# ControlAccess.net
KiCad netlist of a schematic drawn in Altium Designer
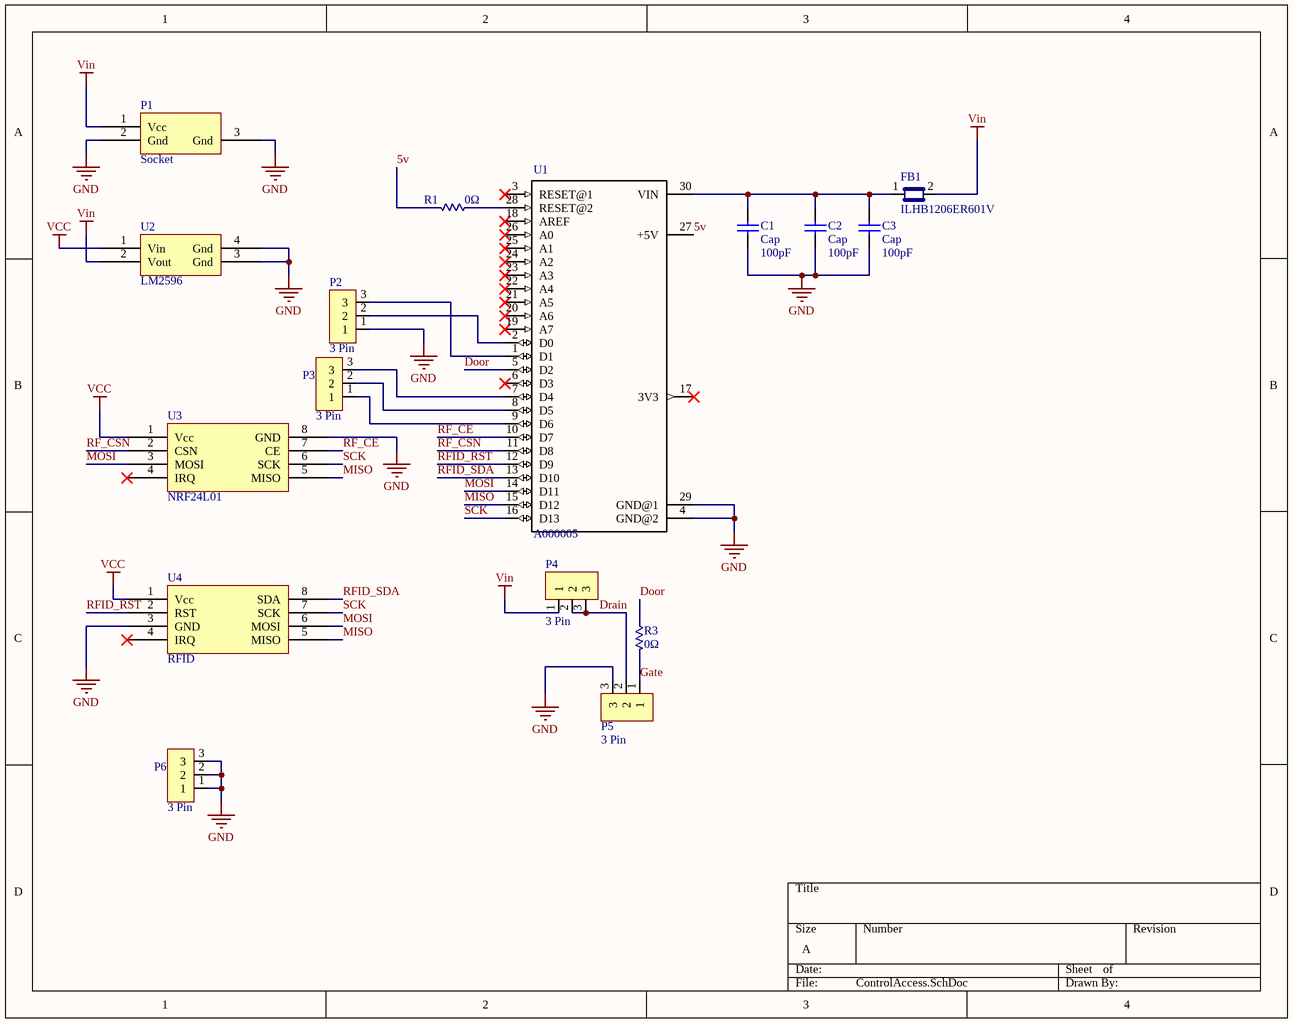
[diagram p0: ControlAccess.SchDoc]

(export (version "E")
  (design (tool "Eeschema 10.0.6"))
  (components
    (comp (ref "C1")
      (value "Cap")
      (footprint "RAD-0.3")
      (description "Capacitor")
      (fields (field (name "ALTIUM_VALUE") "100pF") (field (name "PUBLISHER") "Altium Limited"))
      (libsource (lib "Miscellaneous Devices") (part "Cap"))
    )
    (comp (ref "C2")
      (value "Cap")
      (footprint "RAD-0.3")
      (description "Capacitor")
      (fields (field (name "ALTIUM_VALUE") "100pF") (field (name "PUBLISHER") "Altium Limited"))
      (libsource (lib "Miscellaneous Devices") (part "Cap"))
    )
    (comp (ref "C3")
      (value "Cap")
      (footprint "RAD-0.3")
      (description "Capacitor")
      (fields (field (name "ALTIUM_VALUE") "100pF") (field (name "PUBLISHER") "Altium Limited"))
      (libsource (lib "Miscellaneous Devices") (part "Cap"))
    )
    (comp (ref "FB1")
      (value "ILHB1206ER601V")
      (footprint "FB1206")
      (description "Ferrite Beads Multi-Layer High Current 600Ohm 25% 100MHz 2.5A 100mOhm DCR 1206 T/R")
      (fields (field (name "MANUFACTURER") "Vishay"))
      (libsource (lib "ControlAccessLib") (part "ILHB1206ER601V"))
    )
    (comp (ref "P1")
      (value "Socket")
      (footprint "Clema")
      (libsource (lib "ControlAccessLib") (part "Socket"))
    )
    (comp (ref "P2")
      (value "3 Pin")
      (footprint "PIN_HEADER_3")
      (description "Headers & Wire Housings 02 SIL VERTICAL PIN HEADER TIN")
      (fields (field (name "MANUFACTURER") "Harwin") (field (name "MANUFACTURER PART NUMBER") "M20-9990246"))
      (libsource (lib "ControlAccessLib") (part "M20-9990246"))
    )
    (comp (ref "P3")
      (value "3 Pin")
      (footprint "PIN_HEADER_3")
      (description "Headers & Wire Housings 02 SIL VERTICAL PIN HEADER TIN")
      (fields (field (name "MANUFACTURER") "Harwin") (field (name "MANUFACTURER PART NUMBER") "M20-9990246"))
      (libsource (lib "ControlAccessLib") (part "M20-9990246"))
    )
    (comp (ref "P4")
      (value "3 Pin")
      (footprint "PIN_HEADER_3")
      (description "Headers & Wire Housings 02 SIL VERTICAL PIN HEADER TIN")
      (fields (field (name "MANUFACTURER") "Harwin") (field (name "MANUFACTURER PART NUMBER") "M20-9990246"))
      (libsource (lib "") (part "M20-9990246_2"))
    )
    (comp (ref "P5")
      (value "3 Pin")
      (footprint "PIN_HEADER_3")
      (description "Headers & Wire Housings 02 SIL VERTICAL PIN HEADER TIN")
      (fields (field (name "MANUFACTURER") "Harwin") (field (name "MANUFACTURER PART NUMBER") "M20-9990246"))
      (libsource (lib "") (part "M20-9990246_1"))
    )
    (comp (ref "P6")
      (value "3 Pin")
      (footprint "PIN_HEADER_3")
      (description "Headers & Wire Housings 02 SIL VERTICAL PIN HEADER TIN")
      (fields (field (name "MANUFACTURER") "Harwin") (field (name "MANUFACTURER PART NUMBER") "M20-9990246"))
      (libsource (lib "ControlAccessLib") (part "M20-9990246"))
    )
    (comp (ref "R1")
      (value "0Ω")
      (footprint "RES0805")
      (description "RES SMD 10K OHM 1% 1/10W 0805")
      (fields
        (field (name "MANUFACTURER") "Bourns")
        (field (name "MANUFACTURER PART NUMBER") "CRT0805-FZ-1002ELF")
      )
      (libsource (lib "ControlAccessLib") (part "CRT0805-FZ-1002ELF"))
    )
    (comp (ref "R3")
      (value "0Ω")
      (footprint "RES0805")
      (description "RES SMD 10K OHM 1% 1/10W 0805")
      (fields
        (field (name "MANUFACTURER") "Bourns")
        (field (name "MANUFACTURER PART NUMBER") "CRT0805-FZ-1002ELF")
      )
      (libsource (lib "ControlAccessLib") (part "CRT0805-FZ-1002ELF"))
    )
    (comp (ref "U1")
      (value "A000005")
      (footprint "ARDUINO_A000005")
      (description "MICRO, ARDUINO NANO 3.0, MINI-B USB, ATmega328, 0.1DIP, ICSP HDR")
      (fields (field (name "MF") "Arduino"))
      (libsource (lib "ControlAccessLib") (part "A000005"))
    )
    (comp (ref "U2")
      (value "LM2596")
      (footprint "LM2596")
      (libsource (lib "ControlAccessLib") (part "LM2596"))
    )
    (comp (ref "U3")
      (value "NRF24L01")
      (footprint "NRF24L01")
      (libsource (lib "ControlAccessLib") (part "NRF24L01"))
    )
    (comp (ref "U4") (value "RFID") (footprint "RFID") (libsource (lib "ControlAccessLib") (part "RFID")))
  )
  (nets
    (net (code "1") (name "/5v") (class "Default")
      (node (ref "R1") (pin "1") (pinfunction "1_1") (pintype "passive"))
      (node (ref "U1") (pin "27") (pinfunction "+5V_27") (pintype "power_in"))
    )
    (net (code "2") (name "/Door") (class "Default")
      (node (ref "R3") (pin "2") (pinfunction "2_2") (pintype "passive"))
      (node (ref "U1") (pin "5") (pinfunction "D2_5") (pintype "bidirectional"))
    )
    (net (code "3") (name "/Drain") (class "Default")
      (node (ref "P4") (pin "2") (pinfunction "2_2") (pintype "passive"))
      (node (ref "P4") (pin "3") (pinfunction "3_3") (pintype "passive"))
      (node (ref "P5") (pin "2") (pinfunction "2_2") (pintype "passive"))
    )
    (net (code "4") (name "/Gate") (class "Default")
      (node (ref "P5") (pin "1") (pinfunction "1_1") (pintype "passive"))
      (node (ref "R3") (pin "1") (pinfunction "1_1") (pintype "passive"))
    )
    (net (code "5") (name "/MISO") (class "Default")
      (node (ref "U1") (pin "15") (pinfunction "D12_15") (pintype "bidirectional"))
      (node (ref "U3") (pin "5") (pinfunction "MISO_5") (pintype "passive"))
      (node (ref "U4") (pin "5") (pinfunction "MISO_5") (pintype "passive"))
    )
    (net (code "6") (name "/MOSI") (class "Default")
      (node (ref "U1") (pin "14") (pinfunction "D11_14") (pintype "bidirectional"))
      (node (ref "U3") (pin "3") (pinfunction "MOSI_3") (pintype "passive"))
      (node (ref "U4") (pin "6") (pinfunction "MOSI_6") (pintype "passive"))
    )
    (net (code "7") (name "/RFID_RST") (class "Default")
      (node (ref "U1") (pin "12") (pinfunction "D9_12") (pintype "bidirectional"))
      (node (ref "U4") (pin "2") (pinfunction "RST_2") (pintype "passive"))
    )
    (net (code "8") (name "/RFID_SDA") (class "Default")
      (node (ref "U1") (pin "13") (pinfunction "D10_13") (pintype "bidirectional"))
      (node (ref "U4") (pin "8") (pinfunction "SDA_8") (pintype "passive"))
    )
    (net (code "9") (name "/RF_CE") (class "Default")
      (node (ref "U1") (pin "10") (pinfunction "D7_10") (pintype "bidirectional"))
      (node (ref "U3") (pin "7") (pinfunction "CE_7") (pintype "passive"))
    )
    (net (code "10") (name "/RF_CSN") (class "Default")
      (node (ref "U1") (pin "11") (pinfunction "D8_11") (pintype "bidirectional"))
      (node (ref "U3") (pin "2") (pinfunction "CSN_2") (pintype "passive"))
    )
    (net (code "11") (name "/SCK") (class "Default")
      (node (ref "U1") (pin "16") (pinfunction "D13_16") (pintype "bidirectional"))
      (node (ref "U3") (pin "6") (pinfunction "SCK_6") (pintype "passive"))
      (node (ref "U4") (pin "7") (pinfunction "SCK_7") (pintype "passive"))
    )
    (net (code "12") (name "GND") (class "Default")
      (node (ref "C1") (pin "1") (pinfunction "1_1") (pintype "passive"))
      (node (ref "C2") (pin "1") (pinfunction "1_1") (pintype "passive"))
      (node (ref "C3") (pin "1") (pinfunction "1_1") (pintype "passive"))
      (node (ref "P1") (pin "2") (pinfunction "Gnd_2") (pintype "passive"))
      (node (ref "P1") (pin "3") (pinfunction "Gnd_3") (pintype "passive"))
      (node (ref "P2") (pin "1") (pinfunction "1_1") (pintype "passive"))
      (node (ref "P5") (pin "3") (pinfunction "3_3") (pintype "passive"))
      (node (ref "P6") (pin "1") (pinfunction "1_1") (pintype "passive"))
      (node (ref "P6") (pin "2") (pinfunction "2_2") (pintype "passive"))
      (node (ref "P6") (pin "3") (pinfunction "3_3") (pintype "passive"))
      (node (ref "U1") (pin "29") (pinfunction "GND@1_29") (pintype "power_in"))
      (node (ref "U1") (pin "4") (pinfunction "GND@2_4") (pintype "power_in"))
      (node (ref "U2") (pin "3") (pinfunction "Gnd_3") (pintype "passive"))
      (node (ref "U2") (pin "4") (pinfunction "Gnd_4") (pintype "passive"))
      (node (ref "U3") (pin "8") (pinfunction "GND_8") (pintype "passive"))
      (node (ref "U4") (pin "3") (pinfunction "GND_3") (pintype "passive"))
    )
    (net (code "13") (name "Net-(U1-D0)") (class "Default")
      (node (ref "P2") (pin "2") (pinfunction "2_2") (pintype "passive"))
      (node (ref "U1") (pin "2") (pinfunction "D0_2") (pintype "bidirectional"))
    )
    (net (code "14") (name "Net-(U1-D1)") (class "Default")
      (node (ref "P2") (pin "3") (pinfunction "3_3") (pintype "passive"))
      (node (ref "U1") (pin "1") (pinfunction "D1_1") (pintype "bidirectional"))
    )
    (net (code "15") (name "Net-(U1-D4)") (class "Default")
      (node (ref "P3") (pin "3") (pinfunction "3_3") (pintype "passive"))
      (node (ref "U1") (pin "7") (pinfunction "D4_7") (pintype "bidirectional"))
    )
    (net (code "16") (name "Net-(U1-D5)") (class "Default")
      (node (ref "P3") (pin "2") (pinfunction "2_2") (pintype "passive"))
      (node (ref "U1") (pin "8") (pinfunction "D5_8") (pintype "bidirectional"))
    )
    (net (code "17") (name "Net-(U1-D6)") (class "Default")
      (node (ref "P3") (pin "1") (pinfunction "1_1") (pintype "passive"))
      (node (ref "U1") (pin "9") (pinfunction "D6_9") (pintype "bidirectional"))
    )
    (net (code "18") (name "Net-(U1-RESET@2)") (class "Default")
      (node (ref "R1") (pin "2") (pinfunction "2_2") (pintype "passive"))
      (node (ref "U1") (pin "28") (pinfunction "RESET@2_28") (pintype "input"))
    )
    (net (code "19") (name "Net-(U1-VIN)") (class "Default")
      (node (ref "C1") (pin "2") (pinfunction "2_2") (pintype "passive"))
      (node (ref "C2") (pin "2") (pinfunction "2_2") (pintype "passive"))
      (node (ref "C3") (pin "2") (pinfunction "2_2") (pintype "passive"))
      (node (ref "FB1") (pin "1") (pinfunction "1_1") (pintype "passive"))
      (node (ref "U1") (pin "30") (pinfunction "VIN_30") (pintype "power_in"))
    )
    (net (code "20") (name "VCC") (class "Default")
      (node (ref "U2") (pin "1") (pinfunction "Vin_1") (pintype "passive"))
      (node (ref "U3") (pin "1") (pinfunction "Vcc_1") (pintype "passive"))
      (node (ref "U4") (pin "1") (pinfunction "Vcc_1") (pintype "passive"))
    )
    (net (code "21") (name "Vin") (class "Default")
      (node (ref "FB1") (pin "2") (pinfunction "2_2") (pintype "passive"))
      (node (ref "P1") (pin "1") (pinfunction "Vcc_1") (pintype "passive"))
      (node (ref "P4") (pin "1") (pinfunction "1_1") (pintype "passive"))
      (node (ref "U2") (pin "2") (pinfunction "Vout_2") (pintype "passive"))
    )
    (net (code "22") (name "unconnected-(U1-3V3-Pad17)") (class "Default")
      (node (ref "U1") (pin "17") (pinfunction "3V3_17") (pintype "output+no_connect"))
    )
    (net (code "23") (name "unconnected-(U1-A0-Pad26)") (class "Default")
      (node (ref "U1") (pin "26") (pinfunction "A0_26") (pintype "input+no_connect"))
    )
    (net (code "24") (name "unconnected-(U1-A1-Pad25)") (class "Default")
      (node (ref "U1") (pin "25") (pinfunction "A1_25") (pintype "input+no_connect"))
    )
    (net (code "25") (name "unconnected-(U1-A2-Pad24)") (class "Default")
      (node (ref "U1") (pin "24") (pinfunction "A2_24") (pintype "input+no_connect"))
    )
    (net (code "26") (name "unconnected-(U1-A3-Pad23)") (class "Default")
      (node (ref "U1") (pin "23") (pinfunction "A3_23") (pintype "input+no_connect"))
    )
    (net (code "27") (name "unconnected-(U1-A4-Pad22)") (class "Default")
      (node (ref "U1") (pin "22") (pinfunction "A4_22") (pintype "input+no_connect"))
    )
    (net (code "28") (name "unconnected-(U1-A5-Pad21)") (class "Default")
      (node (ref "U1") (pin "21") (pinfunction "A5_21") (pintype "input+no_connect"))
    )
    (net (code "29") (name "unconnected-(U1-A6-Pad20)") (class "Default")
      (node (ref "U1") (pin "20") (pinfunction "A6_20") (pintype "input+no_connect"))
    )
    (net (code "30") (name "unconnected-(U1-A7-Pad19)") (class "Default")
      (node (ref "U1") (pin "19") (pinfunction "A7_19") (pintype "input+no_connect"))
    )
    (net (code "31") (name "unconnected-(U1-AREF-Pad18)") (class "Default")
      (node (ref "U1") (pin "18") (pinfunction "AREF_18") (pintype "input+no_connect"))
    )
    (net (code "32") (name "unconnected-(U1-D3-Pad6)") (class "Default")
      (node (ref "U1") (pin "6") (pinfunction "D3_6") (pintype "bidirectional+no_connect"))
    )
    (net (code "33") (name "unconnected-(U1-RESET@1-Pad3)") (class "Default")
      (node (ref "U1") (pin "3") (pinfunction "RESET@1_3") (pintype "input+no_connect"))
    )
    (net (code "34") (name "unconnected-(U3-IRQ-Pad4)") (class "Default")
      (node (ref "U3") (pin "4") (pinfunction "IRQ_4") (pintype "passive+no_connect"))
    )
    (net (code "35") (name "unconnected-(U4-IRQ-Pad4)") (class "Default")
      (node (ref "U4") (pin "4") (pinfunction "IRQ_4") (pintype "passive+no_connect"))
    )
  )
)
